# CONTROL_circuit_for_Junction_Box_v2.net
KiCad netlist of a schematic drawn in EAGLE
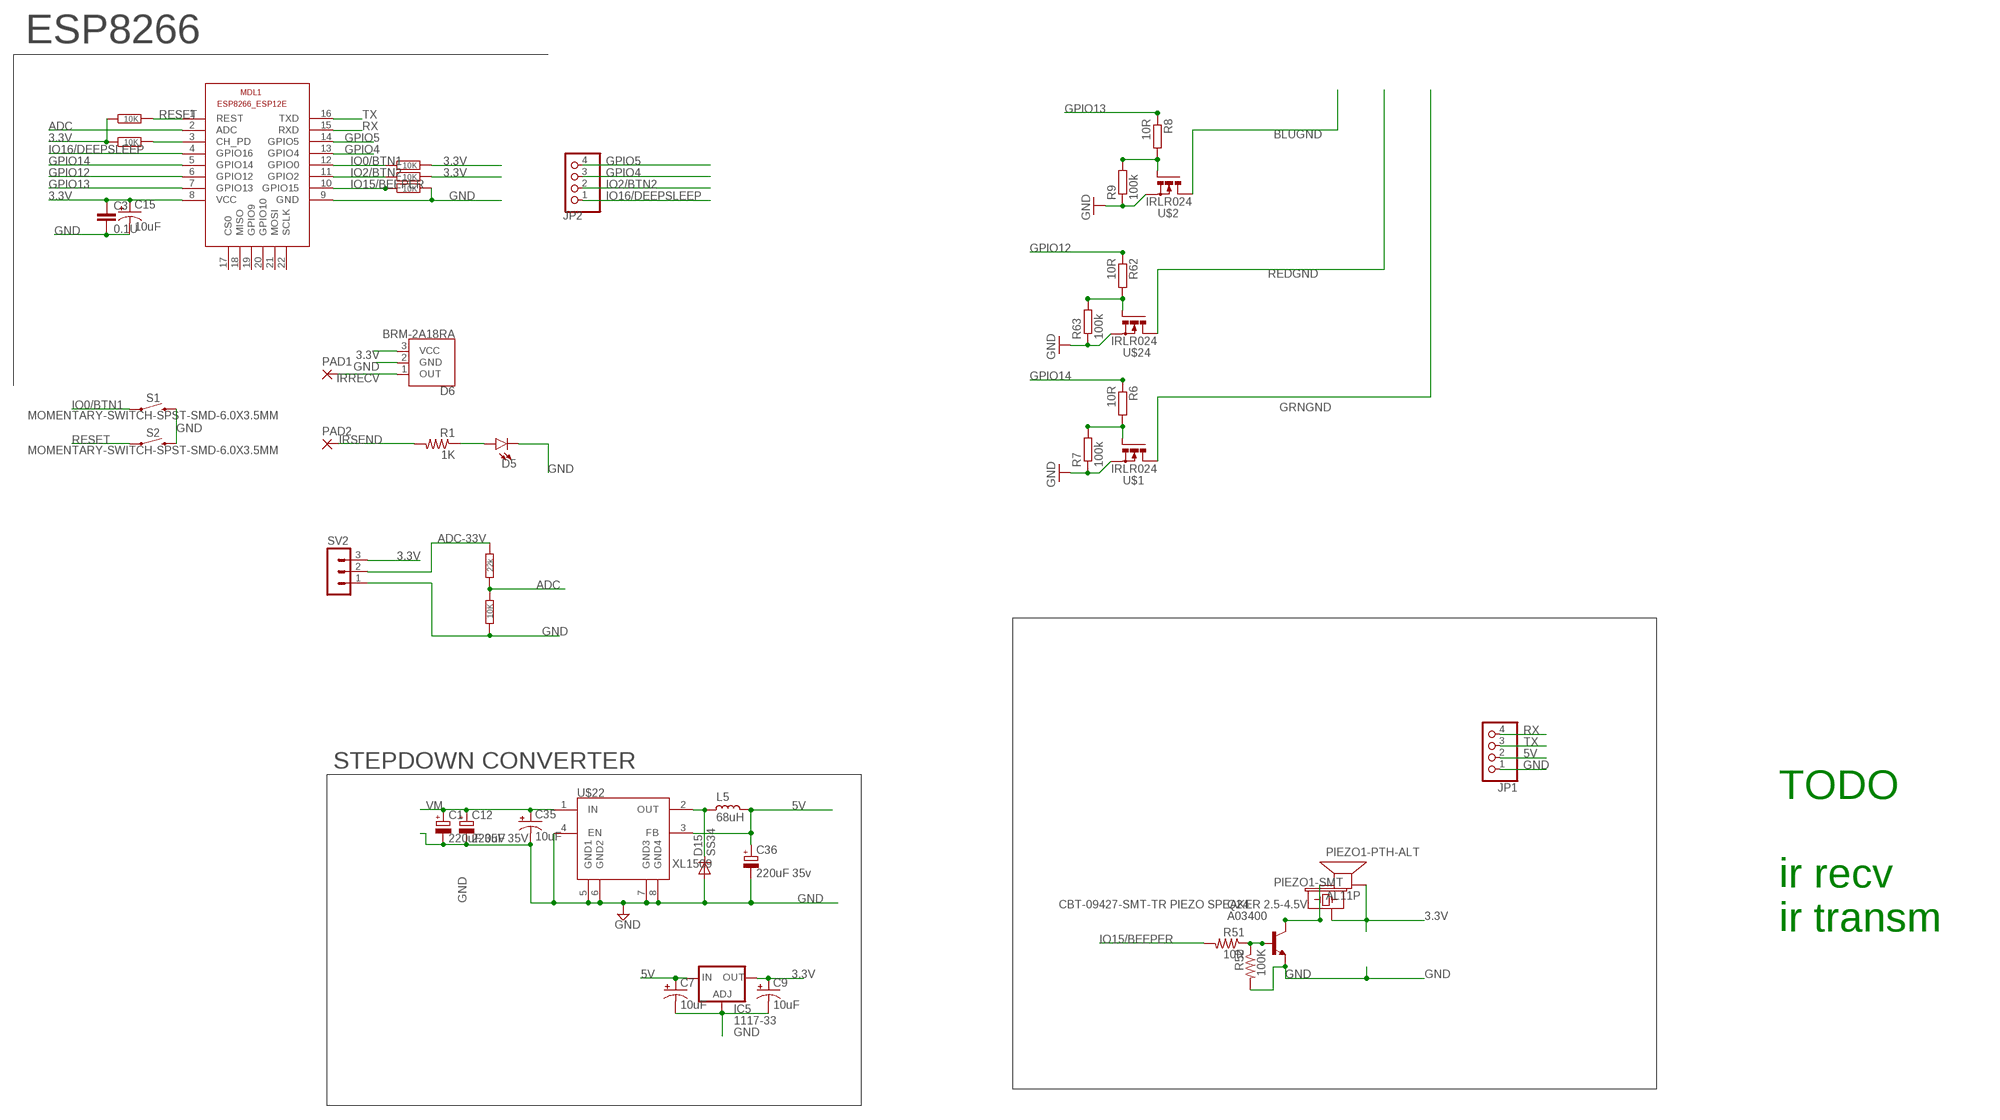
[diagram p0: schematic, sheet 1]

(export (version "E")
  (design (tool "Eeschema 10.0.6"))
  (components
    (comp (ref "C1")
      (value "220uF 35V")
      (footprint "eagle-import:E3,5-8")
      (libsource (lib "eagle-import") (part "CPOL-EUE3.5-8"))
    )
    (comp (ref "C3")
      (value "0.1U")
      (footprint "eagle-import:C1206")
      (libsource (lib "eagle-import") (part "C-EUC1206"))
    )
    (comp (ref "C7")
      (value "10uF")
      (footprint "eagle-import:EIA3216")
      (libsource (lib "eagle-import") (part "CAP_POL1206"))
    )
    (comp (ref "C9")
      (value "10uF")
      (footprint "eagle-import:EIA3216")
      (libsource (lib "eagle-import") (part "CAP_POL1206"))
    )
    (comp (ref "C12")
      (value "220uF 35V")
      (footprint "eagle-import:E3,5-8")
      (libsource (lib "eagle-import") (part "CPOL-EUE3.5-8"))
    )
    (comp (ref "C15")
      (value "10uF")
      (footprint "eagle-import:EIA3216")
      (libsource (lib "eagle-import") (part "CAP_POL1206"))
    )
    (comp (ref "C35")
      (value "10uF")
      (footprint "eagle-import:EIA3216")
      (libsource (lib "eagle-import") (part "CAP_POL1206"))
    )
    (comp (ref "C36")
      (value "220uF 35v")
      (footprint "eagle-import:E3,5-8")
      (libsource (lib "eagle-import") (part "CPOL-EUE3.5-8"))
    )
    (comp (ref "D5")
      (value "LED3MM")
      (footprint "eagle-import:LED_3MM")
      (libsource (lib "eagle-import") (part "LED3MM"))
    )
    (comp (ref "D6")
      (value "BRM-2A18RA")
      (footprint "eagle-import:BRM-2508")
      (libsource (lib "eagle-import") (part "BRM-2A18RA"))
    )
    (comp (ref "D15")
      (value "SS34")
      (footprint "eagle-import:DO-214AC")
      (libsource (lib "eagle-import") (part "DIODE-DO-214AC"))
    )
    (comp (ref "IC5")
      (value "1117-33")
      (footprint "eagle-import:SOT223")
      (libsource (lib "eagle-import") (part "LD117A?S33TR"))
    )
    (comp (ref "JP1")
      (value "PINHD-1X4")
      (footprint "eagle-import:1X04")
      (libsource (lib "eagle-import") (part "PINHD-1X4"))
    )
    (comp (ref "JP2")
      (value "PINHD-1X4")
      (footprint "eagle-import:1X04")
      (libsource (lib "eagle-import") (part "PINHD-1X4"))
    )
    (comp (ref "L5")
      (value "68uH")
      (footprint "eagle-import:CD75")
      (libsource (lib "eagle-import") (part "L_CD75"))
    )
    (comp (ref "MDL1")
      (value "ESP8266-12EESP8266-ESP12E")
      (footprint "eagle-import:ESP8266-ESP12E")
      (libsource (lib "eagle-import") (part "ESP8266-12EESP8266-ESP12E"))
    )
    (comp (ref "PAD1")
      (value "1,6/0,9")
      (footprint "eagle-import:1,6_0,9")
      (libsource (lib "eagle-import") (part "1,6/0,9"))
    )
    (comp (ref "PAD2")
      (value "1,6/0,9")
      (footprint "eagle-import:1,6_0,9")
      (libsource (lib "eagle-import") (part "1,6/0,9"))
    )
    (comp (ref "PIEZO1-PTH-ALT")
      (value "AL11P")
      (footprint "eagle-import:AL11P")
      (libsource (lib "eagle-import") (part "SPEAKER/AL11P"))
    )
    (comp (ref "PIEZO1-SMT")
      (value "CBT-09427-SMT-TR PIEZO SPEAKER 2.5-4.5V")
      (footprint "eagle-import:BUZZER-CCV")
      (libsource (lib "eagle-import") (part "BUZZER-SMD"))
    )
    (comp (ref "Q24")
      (value "A03400")
      (footprint "eagle-import:SOT23-BEC")
      (libsource (lib "eagle-import") (part "BC849SMD"))
    )
    (comp (ref "R1")
      (value "1K")
      (footprint "eagle-import:M1206")
      (libsource (lib "eagle-import") (part "R-US_M1206"))
    )
    (comp (ref "R3")
      (value "22k")
      (footprint "eagle-import:R1206")
      (libsource (lib "eagle-import") (part "R-EU_R1206"))
    )
    (comp (ref "R4")
      (value "10K")
      (footprint "eagle-import:R1206")
      (libsource (lib "eagle-import") (part "R-EU_R1206"))
    )
    (comp (ref "R6")
      (value "10R")
      (footprint "eagle-import:R1206")
      (libsource (lib "eagle-import") (part "resistor_R-EU_R1206"))
    )
    (comp (ref "R7")
      (value "100k")
      (footprint "eagle-import:R1206")
      (libsource (lib "eagle-import") (part "resistor_R-EU_R1206"))
    )
    (comp (ref "R8")
      (value "10R")
      (footprint "eagle-import:R1206")
      (libsource (lib "eagle-import") (part "resistor_R-EU_R1206"))
    )
    (comp (ref "R9")
      (value "100k")
      (footprint "eagle-import:R1206")
      (libsource (lib "eagle-import") (part "resistor_R-EU_R1206"))
    )
    (comp (ref "R11")
      (value "10K")
      (footprint "eagle-import:R1206")
      (libsource (lib "eagle-import") (part "R-EU_R1206"))
    )
    (comp (ref "R12")
      (value "10K")
      (footprint "eagle-import:R1206")
      (libsource (lib "eagle-import") (part "R-EU_R1206"))
    )
    (comp (ref "R28")
      (value "10K")
      (footprint "eagle-import:R1206")
      (libsource (lib "eagle-import") (part "R-EU_R1206"))
    )
    (comp (ref "R29")
      (value "10K")
      (footprint "eagle-import:R1206")
      (libsource (lib "eagle-import") (part "R-EU_R1206"))
    )
    (comp (ref "R31")
      (value "10K")
      (footprint "eagle-import:R1206")
      (libsource (lib "eagle-import") (part "R-EU_R1206"))
    )
    (comp (ref "R51")
      (value "10R")
      (footprint "eagle-import:R1206")
      (libsource (lib "eagle-import") (part "R-US_R1206"))
    )
    (comp (ref "R52")
      (value "100K")
      (footprint "eagle-import:R1206")
      (libsource (lib "eagle-import") (part "R-US_R1206"))
    )
    (comp (ref "R62")
      (value "10R")
      (footprint "eagle-import:R1206")
      (libsource (lib "eagle-import") (part "resistor_R-EU_R1206"))
    )
    (comp (ref "R63")
      (value "100k")
      (footprint "eagle-import:R1206")
      (libsource (lib "eagle-import") (part "resistor_R-EU_R1206"))
    )
    (comp (ref "S1")
      (value "MOMENTARY-SWITCH-SPST-SMD-6.0X3.5MM")
      (footprint "eagle-import:TACTILE_SWITCH_SMD_6.0X3.5MM")
      (libsource (lib "eagle-import") (part "MOMENTARY-SWITCH-SPST-SMD-6.0X3.5MM"))
    )
    (comp (ref "S2")
      (value "MOMENTARY-SWITCH-SPST-SMD-6.0X3.5MM")
      (footprint "eagle-import:TACTILE_SWITCH_SMD_6.0X3.5MM")
      (libsource (lib "eagle-import") (part "MOMENTARY-SWITCH-SPST-SMD-6.0X3.5MM"))
    )
    (comp (ref "SV2")
      (value "MA03-1")
      (footprint "eagle-import:MA03-1")
      (libsource (lib "eagle-import") (part "MA03-1"))
    )
    (comp (ref "U$1")
      (value "IRLR024")
      (footprint "eagle-import:D-PAK_TO252AA")
      (libsource (lib "eagle-import") (part "N-POWER-MOSFETDPAK-MOSFET"))
    )
    (comp (ref "U$2")
      (value "IRLR024")
      (footprint "eagle-import:D-PAK_TO252AA")
      (libsource (lib "eagle-import") (part "N-POWER-MOSFETDPAK-MOSFET"))
    )
    (comp (ref "U$22")
      (value "XL1509")
      (footprint "eagle-import:SO08")
      (libsource (lib "eagle-import") (part "XL1509"))
    )
    (comp (ref "U$24")
      (value "IRLR024")
      (footprint "eagle-import:D-PAK_TO252AA")
      (libsource (lib "eagle-import") (part "N-POWER-MOSFETDPAK-MOSFET"))
    )
  )
  (nets
    (net (code "1") (name "/3.3V") (class "Default")
      (node (ref "C15") (pin "A") (pinfunction "+_A") (pintype "passive"))
      (node (ref "C3") (pin "1") (pinfunction "1_1") (pintype "passive"))
      (node (ref "C9") (pin "A") (pinfunction "+_A") (pintype "passive"))
      (node (ref "D6") (pin "3") (pinfunction "VCC_3") (pintype "bidirectional"))
      (node (ref "IC5") (pin "4") (pinfunction "OUT_4") (pintype "passive"))
      (node (ref "MDL1") (pin "8") (pinfunction "VCC_8") (pintype "bidirectional"))
      (node (ref "PIEZO1-PTH-ALT") (pin "-") (pinfunction "-_-") (pintype "passive"))
      (node (ref "PIEZO1-SMT") (pin "+") (pinfunction "1_+") (pintype "passive"))
      (node (ref "R11") (pin "2") (pinfunction "2_2") (pintype "passive"))
      (node (ref "R12") (pin "2") (pinfunction "2_2") (pintype "passive"))
      (node (ref "R28") (pin "1") (pinfunction "1_1") (pintype "passive"))
      (node (ref "R29") (pin "1") (pinfunction "1_1") (pintype "passive"))
      (node (ref "SV2") (pin "3") (pinfunction "3_3") (pintype "passive"))
    )
    (net (code "2") (name "/5V") (class "Default")
      (node (ref "C36") (pin "+") (pinfunction "+_+") (pintype "passive"))
      (node (ref "C7") (pin "A") (pinfunction "+_A") (pintype "passive"))
      (node (ref "IC5") (pin "3") (pinfunction "IN_3") (pintype "input"))
      (node (ref "JP1") (pin "2") (pinfunction "2_2") (pintype "passive"))
      (node (ref "L5") (pin "1") (pinfunction "1_1") (pintype "passive"))
      (node (ref "U$22") (pin "3") (pinfunction "FB_3") (pintype "bidirectional"))
    )
    (net (code "3") (name "/ADC") (class "Default")
      (node (ref "MDL1") (pin "2") (pinfunction "ADC_2") (pintype "bidirectional"))
      (node (ref "R3") (pin "1") (pinfunction "1_1") (pintype "passive"))
      (node (ref "R4") (pin "2") (pinfunction "2_2") (pintype "passive"))
    )
    (net (code "4") (name "/ADC-33V") (class "Default")
      (node (ref "R3") (pin "2") (pinfunction "2_2") (pintype "passive"))
      (node (ref "SV2") (pin "2") (pinfunction "2_2") (pintype "passive"))
    )
    (net (code "5") (name "/BLUGND") (class "Default")
      (node (ref "U$2") (pin "4") (pinfunction "D_4") (pintype "passive"))
    )
    (net (code "6") (name "/GPIO4") (class "Default")
      (node (ref "JP2") (pin "3") (pinfunction "3_3") (pintype "passive"))
      (node (ref "MDL1") (pin "13") (pinfunction "GPIO4_13") (pintype "bidirectional"))
    )
    (net (code "7") (name "/GPIO5") (class "Default")
      (node (ref "JP2") (pin "4") (pinfunction "4_4") (pintype "passive"))
      (node (ref "MDL1") (pin "14") (pinfunction "GPIO5_14") (pintype "bidirectional"))
    )
    (net (code "8") (name "/GPIO12") (class "Default")
      (node (ref "MDL1") (pin "6") (pinfunction "GPIO12_6") (pintype "bidirectional"))
      (node (ref "R62") (pin "1") (pinfunction "1_1") (pintype "passive"))
    )
    (net (code "9") (name "/GPIO13") (class "Default")
      (node (ref "MDL1") (pin "7") (pinfunction "GPIO13_7") (pintype "bidirectional"))
      (node (ref "R8") (pin "1") (pinfunction "1_1") (pintype "passive"))
    )
    (net (code "10") (name "/GPIO14") (class "Default")
      (node (ref "MDL1") (pin "5") (pinfunction "GPIO14_5") (pintype "bidirectional"))
      (node (ref "R6") (pin "1") (pinfunction "1_1") (pintype "passive"))
    )
    (net (code "11") (name "/GRNGND") (class "Default")
      (node (ref "U$1") (pin "4") (pinfunction "D_4") (pintype "passive"))
    )
    (net (code "12") (name "/IO0{slash}BTN1") (class "Default")
      (node (ref "MDL1") (pin "12") (pinfunction "GPIO0_12") (pintype "bidirectional"))
      (node (ref "R12") (pin "1") (pinfunction "1_1") (pintype "passive"))
      (node (ref "S1") (pin "1") (pinfunction "1_1") (pintype "passive"))
    )
    (net (code "13") (name "/IO2{slash}BTN2") (class "Default")
      (node (ref "JP2") (pin "2") (pinfunction "2_2") (pintype "passive"))
      (node (ref "MDL1") (pin "11") (pinfunction "GPIO2_11") (pintype "bidirectional"))
      (node (ref "R11") (pin "1") (pinfunction "1_1") (pintype "passive"))
    )
    (net (code "14") (name "/IO15{slash}BEEPER") (class "Default")
      (node (ref "MDL1") (pin "10") (pinfunction "GPIO15_10") (pintype "bidirectional"))
      (node (ref "R31") (pin "1") (pinfunction "1_1") (pintype "passive"))
      (node (ref "R51") (pin "2") (pinfunction "2_2") (pintype "passive"))
    )
    (net (code "15") (name "/IO16{slash}DEEPSLEEP") (class "Default")
      (node (ref "JP2") (pin "1") (pinfunction "1_1") (pintype "passive"))
      (node (ref "MDL1") (pin "4") (pinfunction "GPIO16_4") (pintype "bidirectional"))
    )
    (net (code "16") (name "/IRRECV") (class "Default")
      (node (ref "D6") (pin "1") (pinfunction "OUT_1") (pintype "bidirectional"))
      (node (ref "PAD1") (pin "1") (pinfunction "P_1") (pintype "passive"))
    )
    (net (code "17") (name "/IRSEND") (class "Default")
      (node (ref "PAD2") (pin "1") (pinfunction "P_1") (pintype "passive"))
      (node (ref "R1") (pin "2") (pinfunction "2_2") (pintype "passive"))
    )
    (net (code "18") (name "/REDGND") (class "Default")
      (node (ref "U$24") (pin "4") (pinfunction "D_4") (pintype "passive"))
    )
    (net (code "19") (name "/RESET") (class "Default")
      (node (ref "MDL1") (pin "1") (pinfunction "REST_1") (pintype "bidirectional"))
      (node (ref "R29") (pin "2") (pinfunction "2_2") (pintype "passive"))
      (node (ref "S2") (pin "1") (pinfunction "1_1") (pintype "passive"))
    )
    (net (code "20") (name "/RX") (class "Default")
      (node (ref "JP1") (pin "4") (pinfunction "4_4") (pintype "passive"))
      (node (ref "MDL1") (pin "15") (pinfunction "RXD_15") (pintype "bidirectional"))
    )
    (net (code "21") (name "/TX") (class "Default")
      (node (ref "JP1") (pin "3") (pinfunction "3_3") (pintype "passive"))
      (node (ref "MDL1") (pin "16") (pinfunction "TXD_16") (pintype "bidirectional"))
    )
    (net (code "22") (name "/VM") (class "Default")
      (node (ref "C1") (pin "+") (pinfunction "+_+") (pintype "passive"))
      (node (ref "C12") (pin "+") (pinfunction "+_+") (pintype "passive"))
      (node (ref "C35") (pin "A") (pinfunction "+_A") (pintype "passive"))
      (node (ref "U$22") (pin "1") (pinfunction "IN_1") (pintype "bidirectional"))
    )
    (net (code "23") (name "GND") (class "Default")
      (node (ref "C1") (pin "-") (pinfunction "-_-") (pintype "passive"))
      (node (ref "C12") (pin "-") (pinfunction "-_-") (pintype "passive"))
      (node (ref "C15") (pin "C") (pinfunction "-_C") (pintype "passive"))
      (node (ref "C3") (pin "2") (pinfunction "2_2") (pintype "passive"))
      (node (ref "C35") (pin "C") (pinfunction "-_C") (pintype "passive"))
      (node (ref "C36") (pin "-") (pinfunction "-_-") (pintype "passive"))
      (node (ref "C7") (pin "C") (pinfunction "-_C") (pintype "passive"))
      (node (ref "C9") (pin "C") (pinfunction "-_C") (pintype "passive"))
      (node (ref "D15") (pin "2") (pinfunction "A_2") (pintype "passive"))
      (node (ref "D5") (pin "K") (pinfunction "C_K") (pintype "passive"))
      (node (ref "D6") (pin "2") (pinfunction "GND_2") (pintype "bidirectional"))
      (node (ref "IC5") (pin "1") (pinfunction "ADJ_1") (pintype "input"))
      (node (ref "JP1") (pin "1") (pinfunction "1_1") (pintype "passive"))
      (node (ref "MDL1") (pin "9") (pinfunction "GND_9") (pintype "bidirectional"))
      (node (ref "Q24") (pin "E") (pinfunction "E_E") (pintype "passive"))
      (node (ref "R31") (pin "2") (pinfunction "2_2") (pintype "passive"))
      (node (ref "R4") (pin "1") (pinfunction "1_1") (pintype "passive"))
      (node (ref "R52") (pin "2") (pinfunction "2_2") (pintype "passive"))
      (node (ref "R63") (pin "1") (pinfunction "1_1") (pintype "passive"))
      (node (ref "R7") (pin "1") (pinfunction "1_1") (pintype "passive"))
      (node (ref "R9") (pin "1") (pinfunction "1_1") (pintype "passive"))
      (node (ref "S1") (pin "2") (pinfunction "2_2") (pintype "passive"))
      (node (ref "S2") (pin "2") (pinfunction "2_2") (pintype "passive"))
      (node (ref "SV2") (pin "1") (pinfunction "1_1") (pintype "passive"))
      (node (ref "U$1") (pin "3") (pinfunction "S_3") (pintype "passive"))
      (node (ref "U$2") (pin "3") (pinfunction "S_3") (pintype "passive"))
      (node (ref "U$22") (pin "4") (pinfunction "EN_4") (pintype "bidirectional"))
      (node (ref "U$22") (pin "5") (pinfunction "GND1_5") (pintype "bidirectional"))
      (node (ref "U$22") (pin "6") (pinfunction "GND2_6") (pintype "bidirectional"))
      (node (ref "U$22") (pin "7") (pinfunction "GND3_7") (pintype "bidirectional"))
      (node (ref "U$22") (pin "8") (pinfunction "GND4_8") (pintype "bidirectional"))
      (node (ref "U$24") (pin "3") (pinfunction "S_3") (pintype "passive"))
    )
    (net (code "24") (name "Net-(D5-PadA)") (class "Default")
      (node (ref "D5") (pin "A") (pinfunction "A_A") (pintype "passive"))
      (node (ref "R1") (pin "1") (pinfunction "1_1") (pintype "passive"))
    )
    (net (code "25") (name "Net-(D15-C)") (class "Default")
      (node (ref "D15") (pin "1") (pinfunction "C_1") (pintype "passive"))
      (node (ref "L5") (pin "2") (pinfunction "2_2") (pintype "passive"))
      (node (ref "U$22") (pin "2") (pinfunction "OUT_2") (pintype "bidirectional"))
    )
    (net (code "26") (name "Net-(MDL1-CH_PD)") (class "Default")
      (node (ref "MDL1") (pin "3") (pinfunction "CH_PD_3") (pintype "bidirectional"))
      (node (ref "R28") (pin "2") (pinfunction "2_2") (pintype "passive"))
    )
    (net (code "27") (name "Net-(PIEZO1-SMT-2)") (class "Default")
      (node (ref "PIEZO1-PTH-ALT") (pin "+") (pinfunction "+_+") (pintype "passive"))
      (node (ref "PIEZO1-SMT") (pin "-") (pinfunction "2_-") (pintype "passive"))
      (node (ref "Q24") (pin "C") (pinfunction "C_C") (pintype "passive"))
    )
    (net (code "28") (name "Net-(Q24-PadB)") (class "Default")
      (node (ref "Q24") (pin "B") (pinfunction "B_B") (pintype "passive"))
      (node (ref "R51") (pin "1") (pinfunction "1_1") (pintype "passive"))
      (node (ref "R52") (pin "1") (pinfunction "1_1") (pintype "passive"))
    )
    (net (code "29") (name "Net-(U$1-G)") (class "Default")
      (node (ref "R6") (pin "2") (pinfunction "2_2") (pintype "passive"))
      (node (ref "R7") (pin "2") (pinfunction "2_2") (pintype "passive"))
      (node (ref "U$1") (pin "1") (pinfunction "G_1") (pintype "passive"))
    )
    (net (code "30") (name "Net-(U$2-G)") (class "Default")
      (node (ref "R8") (pin "2") (pinfunction "2_2") (pintype "passive"))
      (node (ref "R9") (pin "2") (pinfunction "2_2") (pintype "passive"))
      (node (ref "U$2") (pin "1") (pinfunction "G_1") (pintype "passive"))
    )
    (net (code "31") (name "Net-(U$24-G)") (class "Default")
      (node (ref "R62") (pin "2") (pinfunction "2_2") (pintype "passive"))
      (node (ref "R63") (pin "2") (pinfunction "2_2") (pintype "passive"))
      (node (ref "U$24") (pin "1") (pinfunction "G_1") (pintype "passive"))
    )
    (net (code "32") (name "unconnected-(MDL1-CS0-Pad17)") (class "Default")
      (node (ref "MDL1") (pin "17") (pinfunction "CS0_17") (pintype "bidirectional"))
    )
    (net (code "33") (name "unconnected-(MDL1-GPIO9-Pad19)") (class "Default")
      (node (ref "MDL1") (pin "19") (pinfunction "GPIO9_19") (pintype "bidirectional"))
    )
    (net (code "34") (name "unconnected-(MDL1-GPIO10-Pad20)") (class "Default")
      (node (ref "MDL1") (pin "20") (pinfunction "GPIO10_20") (pintype "bidirectional"))
    )
    (net (code "35") (name "unconnected-(MDL1-MISO-Pad18)") (class "Default")
      (node (ref "MDL1") (pin "18") (pinfunction "MISO_18") (pintype "bidirectional"))
    )
    (net (code "36") (name "unconnected-(MDL1-MOSI-Pad21)") (class "Default")
      (node (ref "MDL1") (pin "21") (pinfunction "MOSI_21") (pintype "bidirectional"))
    )
    (net (code "37") (name "unconnected-(MDL1-SCLK-Pad22)") (class "Default")
      (node (ref "MDL1") (pin "22") (pinfunction "SCLK_22") (pintype "bidirectional"))
    )
  )
)
